# Kinen_Expansion.net
KiCad netlist of a schematic drawn in Altium Designer
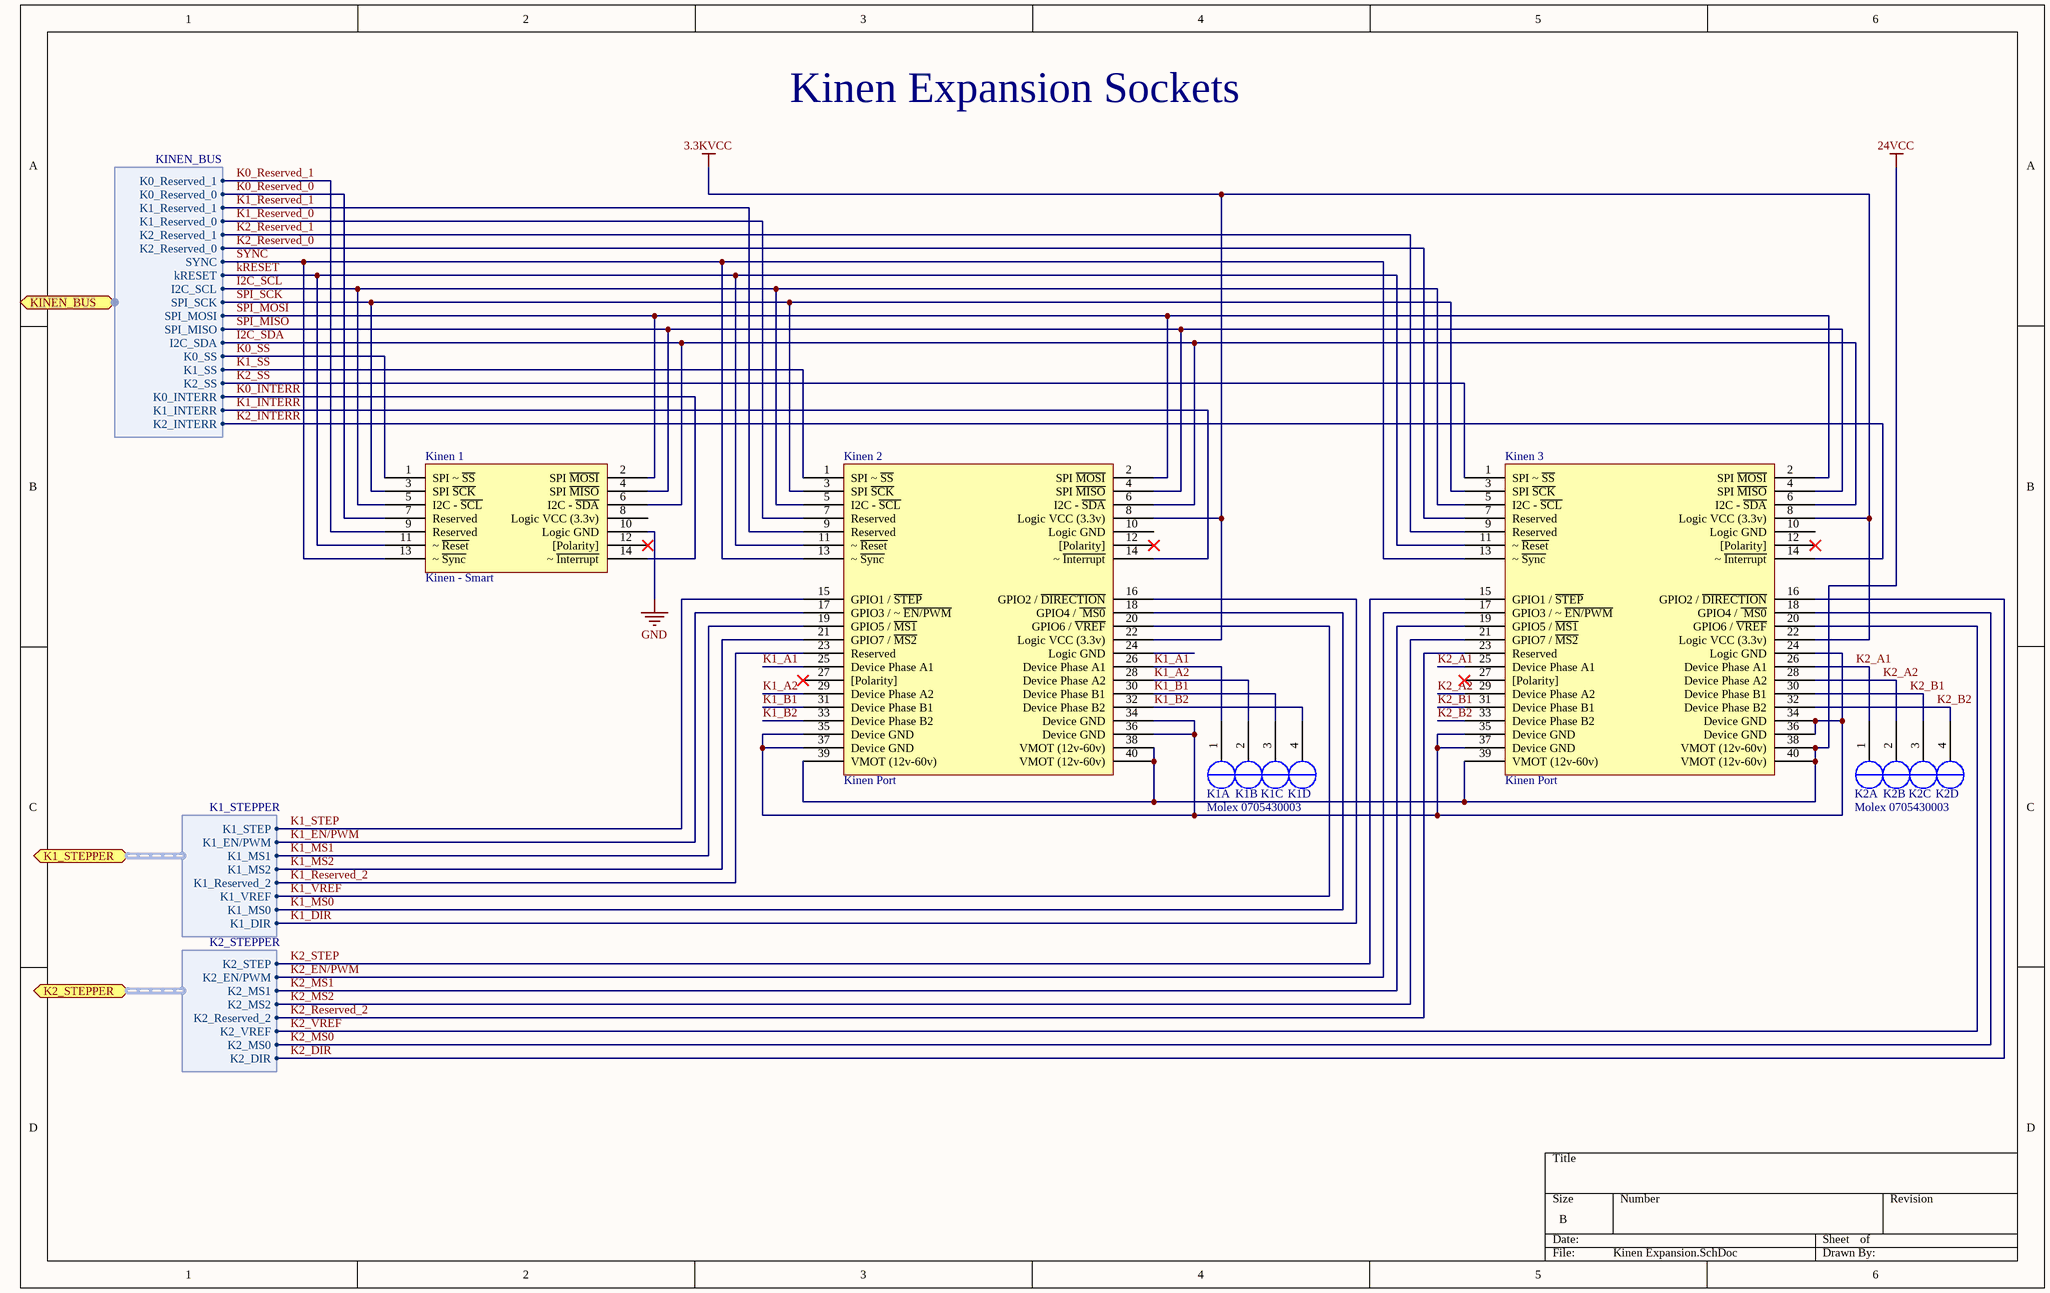
[diagram p0: Kinen Expansion.SchDoc]

(export (version "E")
  (design (tool "Eeschema 10.0.6"))
  (components
    (comp (ref "K1")
      (value "Molex 0705430003")
      (footprint "Molex 0705430003")
      (description "Molex 4 Pin Clip Connector")
      (libsource (lib "") (part "Molex 0705430003 Alt_2"))
    )
    (comp (ref "K2")
      (value "Molex 0705430003")
      (footprint "Molex 0705430003")
      (description "Molex 4 Pin Clip Connector")
      (libsource (lib "ZMBo Schematic Library") (part "Molex 0705430003 Alt"))
    )
    (comp (ref "Kinen 1")
      (value "Kinen - Smart")
      (footprint "Kinen Port - Smart - MOBO")
      (libsource (lib "ZMBo Schematic Library") (part "Kinen - Smart"))
    )
    (comp (ref "Kinen 2")
      (value "Kinen Port")
      (footprint "Kinen Port - MOBO")
      (libsource (lib "ZMBo Schematic Library") (part "Kinen Device NEW"))
    )
    (comp (ref "Kinen 3")
      (value "Kinen Port")
      (footprint "Kinen Port - MOBO")
      (libsource (lib "ZMBo Schematic Library") (part "Kinen Device NEW"))
    )
  )
  (nets
    (net (code "4") (name "/I2C_SCL") (class "Default")
      (node (ref "Kinen 1") (pin "5") (pinfunction "I2C_-_~{SCL}_5") (pintype "passive"))
      (node (ref "Kinen 2") (pin "5") (pinfunction "I2C_-_~{SCL}_5") (pintype "passive"))
      (node (ref "Kinen 3") (pin "5") (pinfunction "I2C_-_~{SCL}_5") (pintype "passive"))
    )
    (net (code "5") (name "/I2C_SDA") (class "Default")
      (node (ref "Kinen 1") (pin "6") (pinfunction "I2C_-_~{SDA}_6") (pintype "passive"))
      (node (ref "Kinen 2") (pin "6") (pinfunction "I2C_-_~{SDA}_6") (pintype "passive"))
      (node (ref "Kinen 3") (pin "6") (pinfunction "I2C_-_~{SDA}_6") (pintype "passive"))
    )
    (net (code "6") (name "/K0_INTERR") (class "Default")
      (node (ref "Kinen 1") (pin "14") (pinfunction "~_~{Interrupt}_14") (pintype "passive"))
    )
    (net (code "7") (name "/K0_Reserved_0") (class "Default")
      (node (ref "Kinen 1") (pin "7") (pinfunction "Reserved_7") (pintype "passive"))
    )
    (net (code "8") (name "/K0_Reserved_1") (class "Default")
      (node (ref "Kinen 1") (pin "9") (pinfunction "Reserved_9") (pintype "passive"))
    )
    (net (code "9") (name "/K0_SS") (class "Default")
      (node (ref "Kinen 1") (pin "1") (pinfunction "SPI_~_~{SS}_1") (pintype "passive"))
    )
    (net (code "10") (name "/K1_A1") (class "Default")
      (node (ref "K1") (pin "1") (pinfunction "OUT2B_1") (pintype "passive"))
      (node (ref "Kinen 2") (pin "25") (pinfunction "Device_Phase_A1_25") (pintype "passive"))
      (node (ref "Kinen 2") (pin "26") (pinfunction "Device_Phase_A1_26") (pintype "passive"))
    )
    (net (code "11") (name "/K1_A2") (class "Default")
      (node (ref "K1") (pin "2") (pinfunction "OUT2A_2") (pintype "passive"))
      (node (ref "Kinen 2") (pin "28") (pinfunction "Device_Phase_A2_28") (pintype "passive"))
      (node (ref "Kinen 2") (pin "29") (pinfunction "Device_Phase_A2_29") (pintype "passive"))
    )
    (net (code "12") (name "/K1_B1") (class "Default")
      (node (ref "K1") (pin "3") (pinfunction "OUT1A_3") (pintype "passive"))
      (node (ref "Kinen 2") (pin "30") (pinfunction "Device_Phase_B1_30") (pintype "passive"))
      (node (ref "Kinen 2") (pin "31") (pinfunction "Device_Phase_B1_31") (pintype "passive"))
    )
    (net (code "13") (name "/K1_B2") (class "Default")
      (node (ref "K1") (pin "4") (pinfunction "OUT1B_4") (pintype "passive"))
      (node (ref "Kinen 2") (pin "32") (pinfunction "Device_Phase_B2_32") (pintype "passive"))
      (node (ref "Kinen 2") (pin "33") (pinfunction "Device_Phase_B2_33") (pintype "passive"))
    )
    (net (code "14") (name "/K1_DIR") (class "Default")
      (node (ref "Kinen 2") (pin "16") (pinfunction "GPIO2_/_~{DIRECTION}_16") (pintype "passive"))
    )
    (net (code "15") (name "/K1_EN{slash}PWM") (class "Default")
      (node (ref "Kinen 2") (pin "17") (pinfunction "GPIO3_/_~_~{EN/PWM}_17") (pintype "passive"))
    )
    (net (code "16") (name "/K1_INTERR") (class "Default")
      (node (ref "Kinen 2") (pin "14") (pinfunction "~_~{Interrupt}_14") (pintype "passive"))
    )
    (net (code "17") (name "/K1_MS0") (class "Default")
      (node (ref "Kinen 2") (pin "18") (pinfunction "GPIO4_/_~{_MS0}_18") (pintype "passive"))
    )
    (net (code "18") (name "/K1_MS1") (class "Default")
      (node (ref "Kinen 2") (pin "19") (pinfunction "GPIO5_/_~{MS1}_19") (pintype "passive"))
    )
    (net (code "19") (name "/K1_MS2") (class "Default")
      (node (ref "Kinen 2") (pin "21") (pinfunction "GPIO7_/_~{MS2}_21") (pintype "passive"))
    )
    (net (code "20") (name "/K1_Reserved_0") (class "Default")
      (node (ref "Kinen 2") (pin "7") (pinfunction "Reserved_7") (pintype "passive"))
    )
    (net (code "21") (name "/K1_Reserved_1") (class "Default")
      (node (ref "Kinen 2") (pin "9") (pinfunction "Reserved_9") (pintype "passive"))
    )
    (net (code "22") (name "/K1_Reserved_2") (class "Default")
      (node (ref "Kinen 2") (pin "23") (pinfunction "Reserved_23") (pintype "passive"))
    )
    (net (code "23") (name "/K1_SS") (class "Default")
      (node (ref "Kinen 2") (pin "1") (pinfunction "SPI_~_~{SS}_1") (pintype "passive"))
    )
    (net (code "24") (name "/K1_STEP") (class "Default")
      (node (ref "Kinen 2") (pin "15") (pinfunction "GPIO1_/_~{STEP}_15") (pintype "passive"))
    )
    (net (code "25") (name "/K1_VREF") (class "Default")
      (node (ref "Kinen 2") (pin "20") (pinfunction "GPIO6_/_~{VREF}_20") (pintype "passive"))
    )
    (net (code "26") (name "/K2_A1") (class "Default")
      (node (ref "K2") (pin "1") (pinfunction "OUT2B_1") (pintype "passive"))
      (node (ref "Kinen 3") (pin "25") (pinfunction "Device_Phase_A1_25") (pintype "passive"))
      (node (ref "Kinen 3") (pin "26") (pinfunction "Device_Phase_A1_26") (pintype "passive"))
    )
    (net (code "27") (name "/K2_A2") (class "Default")
      (node (ref "K2") (pin "2") (pinfunction "OUT2A_2") (pintype "passive"))
      (node (ref "Kinen 3") (pin "28") (pinfunction "Device_Phase_A2_28") (pintype "passive"))
      (node (ref "Kinen 3") (pin "29") (pinfunction "Device_Phase_A2_29") (pintype "passive"))
    )
    (net (code "28") (name "/K2_B1") (class "Default")
      (node (ref "K2") (pin "3") (pinfunction "OUT1A_3") (pintype "passive"))
      (node (ref "Kinen 3") (pin "30") (pinfunction "Device_Phase_B1_30") (pintype "passive"))
      (node (ref "Kinen 3") (pin "31") (pinfunction "Device_Phase_B1_31") (pintype "passive"))
    )
    (net (code "29") (name "/K2_B2") (class "Default")
      (node (ref "K2") (pin "4") (pinfunction "OUT1B_4") (pintype "passive"))
      (node (ref "Kinen 3") (pin "32") (pinfunction "Device_Phase_B2_32") (pintype "passive"))
      (node (ref "Kinen 3") (pin "33") (pinfunction "Device_Phase_B2_33") (pintype "passive"))
    )
    (net (code "30") (name "/K2_DIR") (class "Default")
      (node (ref "Kinen 3") (pin "16") (pinfunction "GPIO2_/_~{DIRECTION}_16") (pintype "passive"))
    )
    (net (code "31") (name "/K2_EN{slash}PWM") (class "Default")
      (node (ref "Kinen 3") (pin "17") (pinfunction "GPIO3_/_~_~{EN/PWM}_17") (pintype "passive"))
    )
    (net (code "32") (name "/K2_INTERR") (class "Default")
      (node (ref "Kinen 3") (pin "14") (pinfunction "~_~{Interrupt}_14") (pintype "passive"))
    )
    (net (code "33") (name "/K2_MS0") (class "Default")
      (node (ref "Kinen 3") (pin "18") (pinfunction "GPIO4_/_~{_MS0}_18") (pintype "passive"))
    )
    (net (code "34") (name "/K2_MS1") (class "Default")
      (node (ref "Kinen 3") (pin "19") (pinfunction "GPIO5_/_~{MS1}_19") (pintype "passive"))
    )
    (net (code "35") (name "/K2_MS2") (class "Default")
      (node (ref "Kinen 3") (pin "21") (pinfunction "GPIO7_/_~{MS2}_21") (pintype "passive"))
    )
    (net (code "36") (name "/K2_Reserved_0") (class "Default")
      (node (ref "Kinen 3") (pin "7") (pinfunction "Reserved_7") (pintype "passive"))
    )
    (net (code "37") (name "/K2_Reserved_1") (class "Default")
      (node (ref "Kinen 3") (pin "9") (pinfunction "Reserved_9") (pintype "passive"))
    )
    (net (code "38") (name "/K2_Reserved_2") (class "Default")
      (node (ref "Kinen 3") (pin "23") (pinfunction "Reserved_23") (pintype "passive"))
    )
    (net (code "39") (name "/K2_SS") (class "Default")
      (node (ref "Kinen 3") (pin "1") (pinfunction "SPI_~_~{SS}_1") (pintype "passive"))
    )
    (net (code "40") (name "/K2_STEP") (class "Default")
      (node (ref "Kinen 3") (pin "15") (pinfunction "GPIO1_/_~{STEP}_15") (pintype "passive"))
    )
    (net (code "41") (name "/K2_VREF") (class "Default")
      (node (ref "Kinen 3") (pin "20") (pinfunction "GPIO6_/_~{VREF}_20") (pintype "passive"))
    )
    (net (code "42") (name "/SPI_MISO") (class "Default")
      (node (ref "Kinen 1") (pin "4") (pinfunction "SPI_~{MISO}_4") (pintype "passive"))
      (node (ref "Kinen 2") (pin "4") (pinfunction "SPI_~{MISO}_4") (pintype "passive"))
      (node (ref "Kinen 3") (pin "4") (pinfunction "SPI_~{MISO}_4") (pintype "passive"))
    )
    (net (code "43") (name "/SPI_MOSI") (class "Default")
      (node (ref "Kinen 1") (pin "2") (pinfunction "SPI_~{MOSI}_2") (pintype "passive"))
      (node (ref "Kinen 2") (pin "2") (pinfunction "SPI_~{MOSI}_2") (pintype "passive"))
      (node (ref "Kinen 3") (pin "2") (pinfunction "SPI_~{MOSI}_2") (pintype "passive"))
    )
    (net (code "44") (name "/SPI_SCK") (class "Default")
      (node (ref "Kinen 1") (pin "3") (pinfunction "SPI_~{SCK}_3") (pintype "passive"))
      (node (ref "Kinen 2") (pin "3") (pinfunction "SPI_~{SCK}_3") (pintype "passive"))
      (node (ref "Kinen 3") (pin "3") (pinfunction "SPI_~{SCK}_3") (pintype "passive"))
    )
    (net (code "45") (name "/SYNC") (class "Default")
      (node (ref "Kinen 1") (pin "13") (pinfunction "~_~{Sync}_13") (pintype "passive"))
      (node (ref "Kinen 2") (pin "13") (pinfunction "~_~{Sync}_13") (pintype "passive"))
      (node (ref "Kinen 3") (pin "13") (pinfunction "~_~{Sync}_13") (pintype "passive"))
    )
    (net (code "46") (name "/kRESET") (class "Default")
      (node (ref "Kinen 1") (pin "11") (pinfunction "~_~{Reset}_11") (pintype "passive"))
      (node (ref "Kinen 2") (pin "11") (pinfunction "~_~{Reset}_11") (pintype "passive"))
      (node (ref "Kinen 3") (pin "11") (pinfunction "~_~{Reset}_11") (pintype "passive"))
    )
    (net (code "50") (name "3.3KVCC") (class "Default")
      (node (ref "Kinen 2") (pin "22") (pinfunction "Logic_VCC_(3.3v)_22") (pintype "passive"))
      (node (ref "Kinen 2") (pin "8") (pinfunction "Logic_VCC_(3.3v)_8") (pintype "passive"))
      (node (ref "Kinen 3") (pin "22") (pinfunction "Logic_VCC_(3.3v)_22") (pintype "passive"))
      (node (ref "Kinen 3") (pin "8") (pinfunction "Logic_VCC_(3.3v)_8") (pintype "passive"))
    )
    (net (code "51") (name "24VCC") (class "Default")
      (node (ref "Kinen 2") (pin "38") (pinfunction "VMOT_(12v-60v)_38") (pintype "passive"))
      (node (ref "Kinen 2") (pin "39") (pinfunction "VMOT_(12v-60v)_39") (pintype "passive"))
      (node (ref "Kinen 2") (pin "40") (pinfunction "VMOT_(12v-60v)_40") (pintype "passive"))
      (node (ref "Kinen 3") (pin "38") (pinfunction "VMOT_(12v-60v)_38") (pintype "passive"))
      (node (ref "Kinen 3") (pin "39") (pinfunction "VMOT_(12v-60v)_39") (pintype "passive"))
      (node (ref "Kinen 3") (pin "40") (pinfunction "VMOT_(12v-60v)_40") (pintype "passive"))
    )
    (net (code "52") (name "GND") (class "Default")
      (node (ref "Kinen 1") (pin "10") (pinfunction "Logic_GND_10") (pintype "passive"))
    )
    (net (code "53") (name "Net-(Kinen 2-Device_GND-Pad34)") (class "Default")
      (node (ref "Kinen 2") (pin "34") (pinfunction "Device_GND_34") (pintype "passive"))
      (node (ref "Kinen 2") (pin "35") (pinfunction "Device_GND_35") (pintype "passive"))
      (node (ref "Kinen 2") (pin "36") (pinfunction "Device_GND_36") (pintype "passive"))
      (node (ref "Kinen 2") (pin "37") (pinfunction "Device_GND_37") (pintype "passive"))
      (node (ref "Kinen 3") (pin "24") (pinfunction "Logic_GND_24") (pintype "passive"))
      (node (ref "Kinen 3") (pin "34") (pinfunction "Device_GND_34") (pintype "passive"))
      (node (ref "Kinen 3") (pin "35") (pinfunction "Device_GND_35") (pintype "passive"))
      (node (ref "Kinen 3") (pin "36") (pinfunction "Device_GND_36") (pintype "passive"))
      (node (ref "Kinen 3") (pin "37") (pinfunction "Device_GND_37") (pintype "passive"))
    )
    (net (code "54") (name "unconnected-(Kinen 1-Logic_VCC_(3.3v)-Pad8)") (class "Default")
      (node (ref "Kinen 1") (pin "8") (pinfunction "Logic_VCC_(3.3v)_8") (pintype "passive"))
    )
    (net (code "55") (name "unconnected-(Kinen 1-[Polarity]-Pad12)") (class "Default")
      (node (ref "Kinen 1") (pin "12") (pinfunction "[Polarity]_12") (pintype "passive+no_connect"))
    )
    (net (code "56") (name "unconnected-(Kinen 2-Logic_GND-Pad10)") (class "Default")
      (node (ref "Kinen 2") (pin "10") (pinfunction "Logic_GND_10") (pintype "passive"))
    )
    (net (code "57") (name "unconnected-(Kinen 2-Logic_GND-Pad24)") (class "Default")
      (node (ref "Kinen 2") (pin "24") (pinfunction "Logic_GND_24") (pintype "passive"))
    )
    (net (code "58") (name "unconnected-(Kinen 2-[Polarity]-Pad12)") (class "Default")
      (node (ref "Kinen 2") (pin "12") (pinfunction "[Polarity]_12") (pintype "passive+no_connect"))
    )
    (net (code "59") (name "unconnected-(Kinen 2-[Polarity]-Pad27)") (class "Default")
      (node (ref "Kinen 2") (pin "27") (pinfunction "[Polarity]_27") (pintype "passive+no_connect"))
    )
    (net (code "60") (name "unconnected-(Kinen 3-Logic_GND-Pad10)") (class "Default")
      (node (ref "Kinen 3") (pin "10") (pinfunction "Logic_GND_10") (pintype "passive"))
    )
    (net (code "61") (name "unconnected-(Kinen 3-[Polarity]-Pad12)") (class "Default")
      (node (ref "Kinen 3") (pin "12") (pinfunction "[Polarity]_12") (pintype "passive+no_connect"))
    )
    (net (code "62") (name "unconnected-(Kinen 3-[Polarity]-Pad27)") (class "Default")
      (node (ref "Kinen 3") (pin "27") (pinfunction "[Polarity]_27") (pintype "passive+no_connect"))
    )
  )
)
